# Schematic_PixelRing.net
KiCad netlist of a schematic drawn in Altium Designer
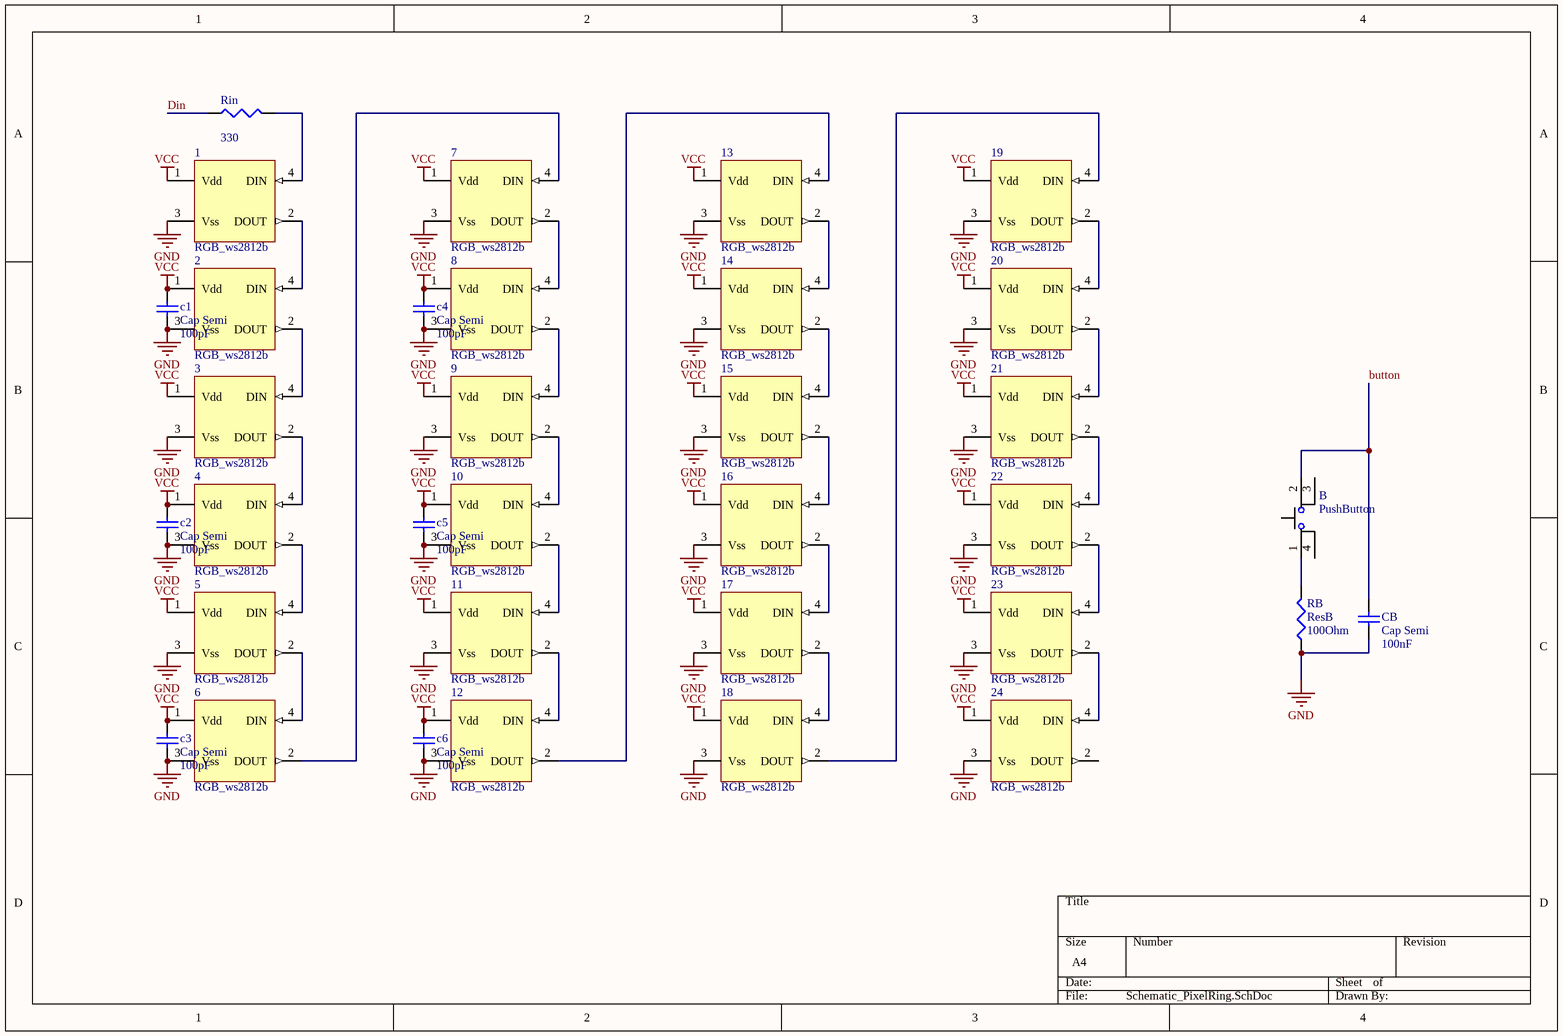
[diagram p0: Schematic_PixelRing.SchDoc]

(export (version "E")
  (design (tool "Eeschema 10.0.6"))
  (components
    (comp (ref "1")
      (value "RGB_ws2812b")
      (footprint "ws2812b")
      (libsource (lib "RGB_Lib") (part "RGB_ws2812b"))
    )
    (comp (ref "2")
      (value "RGB_ws2812b")
      (footprint "ws2812b")
      (libsource (lib "RGB_Lib") (part "RGB_ws2812b"))
    )
    (comp (ref "3")
      (value "RGB_ws2812b")
      (footprint "ws2812b")
      (libsource (lib "RGB_Lib") (part "RGB_ws2812b"))
    )
    (comp (ref "4")
      (value "RGB_ws2812b")
      (footprint "ws2812b")
      (libsource (lib "RGB_Lib") (part "RGB_ws2812b"))
    )
    (comp (ref "5")
      (value "RGB_ws2812b")
      (footprint "ws2812b")
      (libsource (lib "RGB_Lib") (part "RGB_ws2812b"))
    )
    (comp (ref "6")
      (value "RGB_ws2812b")
      (footprint "ws2812b")
      (libsource (lib "RGB_Lib") (part "RGB_ws2812b"))
    )
    (comp (ref "7")
      (value "RGB_ws2812b")
      (footprint "ws2812b")
      (libsource (lib "RGB_Lib") (part "RGB_ws2812b"))
    )
    (comp (ref "8")
      (value "RGB_ws2812b")
      (footprint "ws2812b")
      (libsource (lib "RGB_Lib") (part "RGB_ws2812b"))
    )
    (comp (ref "9")
      (value "RGB_ws2812b")
      (footprint "ws2812b")
      (libsource (lib "RGB_Lib") (part "RGB_ws2812b"))
    )
    (comp (ref "10")
      (value "RGB_ws2812b")
      (footprint "ws2812b")
      (libsource (lib "RGB_Lib") (part "RGB_ws2812b"))
    )
    (comp (ref "11")
      (value "RGB_ws2812b")
      (footprint "ws2812b")
      (libsource (lib "RGB_Lib") (part "RGB_ws2812b"))
    )
    (comp (ref "12")
      (value "RGB_ws2812b")
      (footprint "ws2812b")
      (libsource (lib "RGB_Lib") (part "RGB_ws2812b"))
    )
    (comp (ref "13")
      (value "RGB_ws2812b")
      (footprint "ws2812b")
      (libsource (lib "RGB_Lib") (part "RGB_ws2812b"))
    )
    (comp (ref "14")
      (value "RGB_ws2812b")
      (footprint "ws2812b")
      (libsource (lib "RGB_Lib") (part "RGB_ws2812b"))
    )
    (comp (ref "15")
      (value "RGB_ws2812b")
      (footprint "ws2812b")
      (libsource (lib "RGB_Lib") (part "RGB_ws2812b"))
    )
    (comp (ref "16")
      (value "RGB_ws2812b")
      (footprint "ws2812b")
      (libsource (lib "RGB_Lib") (part "RGB_ws2812b"))
    )
    (comp (ref "17")
      (value "RGB_ws2812b")
      (footprint "ws2812b")
      (libsource (lib "RGB_Lib") (part "RGB_ws2812b"))
    )
    (comp (ref "18")
      (value "RGB_ws2812b")
      (footprint "ws2812b")
      (libsource (lib "RGB_Lib") (part "RGB_ws2812b"))
    )
    (comp (ref "19")
      (value "RGB_ws2812b")
      (footprint "ws2812b")
      (libsource (lib "RGB_Lib") (part "RGB_ws2812b"))
    )
    (comp (ref "20")
      (value "RGB_ws2812b")
      (footprint "ws2812b")
      (libsource (lib "RGB_Lib") (part "RGB_ws2812b"))
    )
    (comp (ref "21")
      (value "RGB_ws2812b")
      (footprint "ws2812b")
      (libsource (lib "RGB_Lib") (part "RGB_ws2812b"))
    )
    (comp (ref "22")
      (value "RGB_ws2812b")
      (footprint "ws2812b")
      (libsource (lib "RGB_Lib") (part "RGB_ws2812b"))
    )
    (comp (ref "23")
      (value "RGB_ws2812b")
      (footprint "ws2812b")
      (libsource (lib "RGB_Lib") (part "RGB_ws2812b"))
    )
    (comp (ref "24")
      (value "RGB_ws2812b")
      (footprint "ws2812b")
      (libsource (lib "RGB_Lib") (part "RGB_ws2812b"))
    )
    (comp (ref "B") (value "PushButton") (footprint "SW 6mm") (libsource (lib "SW_Lib") (part "PushButton")))
    (comp (ref "c1")
      (value "Cap Semi")
      (footprint "6-0805_N")
      (description "Capacitor (Semiconductor SIM Model)")
      (fields (field (name "ALTIUM_VALUE") "100pF") (field (name "PUBLISHER") "Altium Limited"))
      (libsource (lib "Miscellaneous Devices") (part "Cap Semi"))
    )
    (comp (ref "c2")
      (value "Cap Semi")
      (footprint "6-0805_N")
      (description "Capacitor (Semiconductor SIM Model)")
      (fields (field (name "ALTIUM_VALUE") "100pF") (field (name "PUBLISHER") "Altium Limited"))
      (libsource (lib "Miscellaneous Devices") (part "Cap Semi"))
    )
    (comp (ref "c3")
      (value "Cap Semi")
      (footprint "6-0805_N")
      (description "Capacitor (Semiconductor SIM Model)")
      (fields (field (name "ALTIUM_VALUE") "100pF") (field (name "PUBLISHER") "Altium Limited"))
      (libsource (lib "Miscellaneous Devices") (part "Cap Semi"))
    )
    (comp (ref "c4")
      (value "Cap Semi")
      (footprint "6-0805_N")
      (description "Capacitor (Semiconductor SIM Model)")
      (fields (field (name "ALTIUM_VALUE") "100pF") (field (name "PUBLISHER") "Altium Limited"))
      (libsource (lib "Miscellaneous Devices") (part "Cap Semi"))
    )
    (comp (ref "c5")
      (value "Cap Semi")
      (footprint "6-0805_N")
      (description "Capacitor (Semiconductor SIM Model)")
      (fields (field (name "ALTIUM_VALUE") "100pF") (field (name "PUBLISHER") "Altium Limited"))
      (libsource (lib "Miscellaneous Devices") (part "Cap Semi"))
    )
    (comp (ref "c6")
      (value "Cap Semi")
      (footprint "6-0805_N")
      (description "Capacitor (Semiconductor SIM Model)")
      (fields (field (name "ALTIUM_VALUE") "100pF") (field (name "PUBLISHER") "Altium Limited"))
      (libsource (lib "Miscellaneous Devices") (part "Cap Semi"))
    )
    (comp (ref "CB")
      (value "Cap Semi")
      (footprint "6-0805_N")
      (description "Capacitor (Semiconductor SIM Model)")
      (fields (field (name "ALTIUM_VALUE") "100nF") (field (name "PUBLISHER") "Altium Limited"))
      (libsource (lib "Miscellaneous Devices") (part "Cap Semi"))
    )
    (comp (ref "RB")
      (value "ResB")
      (footprint "6-0805_N")
      (description "Resistor")
      (fields (field (name "ALTIUM_VALUE") "100Ohm") (field (name "PUBLISHER") "Altium Limited"))
      (libsource (lib "Miscellaneous Devices") (part "Res3"))
    )
    (comp (ref "Rin")
      (value "330")
      (footprint "6-0805_N")
      (description "Resistor")
      (fields (field (name "PUBLISHER") "Altium Limited"))
      (libsource (lib "Miscellaneous Devices") (part "Res3"))
    )
  )
  (nets
    (net (code "1") (name "/Din") (class "Default")
      (node (ref "Rin") (pin "1") (pinfunction "1_1") (pintype "passive"))
    )
    (net (code "2") (name "/button") (class "Default")
      (node (ref "B") (pin "2") (pinfunction "Gnd_2") (pintype "power_in"))
      (node (ref "CB") (pin "2") (pinfunction "2_2") (pintype "passive"))
    )
    (net (code "3") (name "GND") (class "Default")
      (node (ref "1") (pin "3") (pinfunction "Vss_3") (pintype "power_in"))
      (node (ref "10") (pin "3") (pinfunction "Vss_3") (pintype "power_in"))
      (node (ref "11") (pin "3") (pinfunction "Vss_3") (pintype "power_in"))
      (node (ref "12") (pin "3") (pinfunction "Vss_3") (pintype "power_in"))
      (node (ref "13") (pin "3") (pinfunction "Vss_3") (pintype "power_in"))
      (node (ref "14") (pin "3") (pinfunction "Vss_3") (pintype "power_in"))
      (node (ref "15") (pin "3") (pinfunction "Vss_3") (pintype "power_in"))
      (node (ref "16") (pin "3") (pinfunction "Vss_3") (pintype "power_in"))
      (node (ref "17") (pin "3") (pinfunction "Vss_3") (pintype "power_in"))
      (node (ref "18") (pin "3") (pinfunction "Vss_3") (pintype "power_in"))
      (node (ref "19") (pin "3") (pinfunction "Vss_3") (pintype "power_in"))
      (node (ref "2") (pin "3") (pinfunction "Vss_3") (pintype "power_in"))
      (node (ref "20") (pin "3") (pinfunction "Vss_3") (pintype "power_in"))
      (node (ref "21") (pin "3") (pinfunction "Vss_3") (pintype "power_in"))
      (node (ref "22") (pin "3") (pinfunction "Vss_3") (pintype "power_in"))
      (node (ref "23") (pin "3") (pinfunction "Vss_3") (pintype "power_in"))
      (node (ref "24") (pin "3") (pinfunction "Vss_3") (pintype "power_in"))
      (node (ref "3") (pin "3") (pinfunction "Vss_3") (pintype "power_in"))
      (node (ref "4") (pin "3") (pinfunction "Vss_3") (pintype "power_in"))
      (node (ref "5") (pin "3") (pinfunction "Vss_3") (pintype "power_in"))
      (node (ref "6") (pin "3") (pinfunction "Vss_3") (pintype "power_in"))
      (node (ref "7") (pin "3") (pinfunction "Vss_3") (pintype "power_in"))
      (node (ref "8") (pin "3") (pinfunction "Vss_3") (pintype "power_in"))
      (node (ref "9") (pin "3") (pinfunction "Vss_3") (pintype "power_in"))
      (node (ref "CB") (pin "1") (pinfunction "1_1") (pintype "passive"))
      (node (ref "RB") (pin "1") (pinfunction "1_1") (pintype "passive"))
      (node (ref "c1") (pin "1") (pinfunction "1_1") (pintype "passive"))
      (node (ref "c2") (pin "1") (pinfunction "1_1") (pintype "passive"))
      (node (ref "c3") (pin "1") (pinfunction "1_1") (pintype "passive"))
      (node (ref "c4") (pin "1") (pinfunction "1_1") (pintype "passive"))
      (node (ref "c5") (pin "1") (pinfunction "1_1") (pintype "passive"))
      (node (ref "c6") (pin "1") (pinfunction "1_1") (pintype "passive"))
    )
    (net (code "4") (name "Net-(1-DIN)") (class "Default")
      (node (ref "1") (pin "4") (pinfunction "DIN_4") (pintype "input"))
      (node (ref "Rin") (pin "2") (pinfunction "2_2") (pintype "passive"))
    )
    (net (code "5") (name "Net-(1-DOUT)") (class "Default")
      (node (ref "1") (pin "2") (pinfunction "DOUT_2") (pintype "output"))
      (node (ref "2") (pin "4") (pinfunction "DIN_4") (pintype "input"))
    )
    (net (code "6") (name "Net-(2-DOUT)") (class "Default")
      (node (ref "2") (pin "2") (pinfunction "DOUT_2") (pintype "output"))
      (node (ref "3") (pin "4") (pinfunction "DIN_4") (pintype "input"))
    )
    (net (code "7") (name "Net-(3-DOUT)") (class "Default")
      (node (ref "3") (pin "2") (pinfunction "DOUT_2") (pintype "output"))
      (node (ref "4") (pin "4") (pinfunction "DIN_4") (pintype "input"))
    )
    (net (code "8") (name "Net-(4-DOUT)") (class "Default")
      (node (ref "4") (pin "2") (pinfunction "DOUT_2") (pintype "output"))
      (node (ref "5") (pin "4") (pinfunction "DIN_4") (pintype "input"))
    )
    (net (code "9") (name "Net-(5-DOUT)") (class "Default")
      (node (ref "5") (pin "2") (pinfunction "DOUT_2") (pintype "output"))
      (node (ref "6") (pin "4") (pinfunction "DIN_4") (pintype "input"))
    )
    (net (code "10") (name "Net-(6-DOUT)") (class "Default")
      (node (ref "6") (pin "2") (pinfunction "DOUT_2") (pintype "output"))
      (node (ref "7") (pin "4") (pinfunction "DIN_4") (pintype "input"))
    )
    (net (code "11") (name "Net-(7-DOUT)") (class "Default")
      (node (ref "7") (pin "2") (pinfunction "DOUT_2") (pintype "output"))
      (node (ref "8") (pin "4") (pinfunction "DIN_4") (pintype "input"))
    )
    (net (code "12") (name "Net-(8-DOUT)") (class "Default")
      (node (ref "8") (pin "2") (pinfunction "DOUT_2") (pintype "output"))
      (node (ref "9") (pin "4") (pinfunction "DIN_4") (pintype "input"))
    )
    (net (code "13") (name "Net-(10-DIN)") (class "Default")
      (node (ref "10") (pin "4") (pinfunction "DIN_4") (pintype "input"))
      (node (ref "9") (pin "2") (pinfunction "DOUT_2") (pintype "output"))
    )
    (net (code "14") (name "Net-(10-DOUT)") (class "Default")
      (node (ref "10") (pin "2") (pinfunction "DOUT_2") (pintype "output"))
      (node (ref "11") (pin "4") (pinfunction "DIN_4") (pintype "input"))
    )
    (net (code "15") (name "Net-(11-DOUT)") (class "Default")
      (node (ref "11") (pin "2") (pinfunction "DOUT_2") (pintype "output"))
      (node (ref "12") (pin "4") (pinfunction "DIN_4") (pintype "input"))
    )
    (net (code "16") (name "Net-(12-DOUT)") (class "Default")
      (node (ref "12") (pin "2") (pinfunction "DOUT_2") (pintype "output"))
      (node (ref "13") (pin "4") (pinfunction "DIN_4") (pintype "input"))
    )
    (net (code "17") (name "Net-(13-DOUT)") (class "Default")
      (node (ref "13") (pin "2") (pinfunction "DOUT_2") (pintype "output"))
      (node (ref "14") (pin "4") (pinfunction "DIN_4") (pintype "input"))
    )
    (net (code "18") (name "Net-(14-DOUT)") (class "Default")
      (node (ref "14") (pin "2") (pinfunction "DOUT_2") (pintype "output"))
      (node (ref "15") (pin "4") (pinfunction "DIN_4") (pintype "input"))
    )
    (net (code "19") (name "Net-(15-DOUT)") (class "Default")
      (node (ref "15") (pin "2") (pinfunction "DOUT_2") (pintype "output"))
      (node (ref "16") (pin "4") (pinfunction "DIN_4") (pintype "input"))
    )
    (net (code "20") (name "Net-(16-DOUT)") (class "Default")
      (node (ref "16") (pin "2") (pinfunction "DOUT_2") (pintype "output"))
      (node (ref "17") (pin "4") (pinfunction "DIN_4") (pintype "input"))
    )
    (net (code "21") (name "Net-(17-DOUT)") (class "Default")
      (node (ref "17") (pin "2") (pinfunction "DOUT_2") (pintype "output"))
      (node (ref "18") (pin "4") (pinfunction "DIN_4") (pintype "input"))
    )
    (net (code "22") (name "Net-(18-DOUT)") (class "Default")
      (node (ref "18") (pin "2") (pinfunction "DOUT_2") (pintype "output"))
      (node (ref "19") (pin "4") (pinfunction "DIN_4") (pintype "input"))
    )
    (net (code "23") (name "Net-(19-DOUT)") (class "Default")
      (node (ref "19") (pin "2") (pinfunction "DOUT_2") (pintype "output"))
      (node (ref "20") (pin "4") (pinfunction "DIN_4") (pintype "input"))
    )
    (net (code "24") (name "Net-(20-DOUT)") (class "Default")
      (node (ref "20") (pin "2") (pinfunction "DOUT_2") (pintype "output"))
      (node (ref "21") (pin "4") (pinfunction "DIN_4") (pintype "input"))
    )
    (net (code "25") (name "Net-(21-DOUT)") (class "Default")
      (node (ref "21") (pin "2") (pinfunction "DOUT_2") (pintype "output"))
      (node (ref "22") (pin "4") (pinfunction "DIN_4") (pintype "input"))
    )
    (net (code "26") (name "Net-(22-DOUT)") (class "Default")
      (node (ref "22") (pin "2") (pinfunction "DOUT_2") (pintype "output"))
      (node (ref "23") (pin "4") (pinfunction "DIN_4") (pintype "input"))
    )
    (net (code "27") (name "Net-(23-DOUT)") (class "Default")
      (node (ref "23") (pin "2") (pinfunction "DOUT_2") (pintype "output"))
      (node (ref "24") (pin "4") (pinfunction "DIN_4") (pintype "input"))
    )
    (net (code "28") (name "Net-(B-Gnd-Pad1)") (class "Default")
      (node (ref "B") (pin "1") (pinfunction "Gnd_1") (pintype "power_in"))
      (node (ref "RB") (pin "2") (pinfunction "2_2") (pintype "passive"))
    )
    (net (code "29") (name "VCC") (class "Default")
      (node (ref "1") (pin "1") (pinfunction "Vdd_1") (pintype "power_in"))
      (node (ref "10") (pin "1") (pinfunction "Vdd_1") (pintype "power_in"))
      (node (ref "11") (pin "1") (pinfunction "Vdd_1") (pintype "power_in"))
      (node (ref "12") (pin "1") (pinfunction "Vdd_1") (pintype "power_in"))
      (node (ref "13") (pin "1") (pinfunction "Vdd_1") (pintype "power_in"))
      (node (ref "14") (pin "1") (pinfunction "Vdd_1") (pintype "power_in"))
      (node (ref "15") (pin "1") (pinfunction "Vdd_1") (pintype "power_in"))
      (node (ref "16") (pin "1") (pinfunction "Vdd_1") (pintype "power_in"))
      (node (ref "17") (pin "1") (pinfunction "Vdd_1") (pintype "power_in"))
      (node (ref "18") (pin "1") (pinfunction "Vdd_1") (pintype "power_in"))
      (node (ref "19") (pin "1") (pinfunction "Vdd_1") (pintype "power_in"))
      (node (ref "2") (pin "1") (pinfunction "Vdd_1") (pintype "power_in"))
      (node (ref "20") (pin "1") (pinfunction "Vdd_1") (pintype "power_in"))
      (node (ref "21") (pin "1") (pinfunction "Vdd_1") (pintype "power_in"))
      (node (ref "22") (pin "1") (pinfunction "Vdd_1") (pintype "power_in"))
      (node (ref "23") (pin "1") (pinfunction "Vdd_1") (pintype "power_in"))
      (node (ref "24") (pin "1") (pinfunction "Vdd_1") (pintype "power_in"))
      (node (ref "3") (pin "1") (pinfunction "Vdd_1") (pintype "power_in"))
      (node (ref "4") (pin "1") (pinfunction "Vdd_1") (pintype "power_in"))
      (node (ref "5") (pin "1") (pinfunction "Vdd_1") (pintype "power_in"))
      (node (ref "6") (pin "1") (pinfunction "Vdd_1") (pintype "power_in"))
      (node (ref "7") (pin "1") (pinfunction "Vdd_1") (pintype "power_in"))
      (node (ref "8") (pin "1") (pinfunction "Vdd_1") (pintype "power_in"))
      (node (ref "9") (pin "1") (pinfunction "Vdd_1") (pintype "power_in"))
      (node (ref "c1") (pin "2") (pinfunction "2_2") (pintype "passive"))
      (node (ref "c2") (pin "2") (pinfunction "2_2") (pintype "passive"))
      (node (ref "c3") (pin "2") (pinfunction "2_2") (pintype "passive"))
      (node (ref "c4") (pin "2") (pinfunction "2_2") (pintype "passive"))
      (node (ref "c5") (pin "2") (pinfunction "2_2") (pintype "passive"))
      (node (ref "c6") (pin "2") (pinfunction "2_2") (pintype "passive"))
    )
    (net (code "30") (name "unconnected-(24-DOUT-Pad2)") (class "Default")
      (node (ref "24") (pin "2") (pinfunction "DOUT_2") (pintype "output"))
    )
    (net (code "31") (name "unconnected-(B-Gnd-Pad3)") (class "Default")
      (node (ref "B") (pin "3") (pinfunction "Gnd_3") (pintype "power_in"))
    )
    (net (code "32") (name "unconnected-(B-Gnd-Pad4)") (class "Default")
      (node (ref "B") (pin "4") (pinfunction "Gnd_4") (pintype "power_in"))
    )
  )
)
